# 3y-ym-2xxxy-psu-breakout.net
KiCad netlist of a schematic drawn in EAGLE
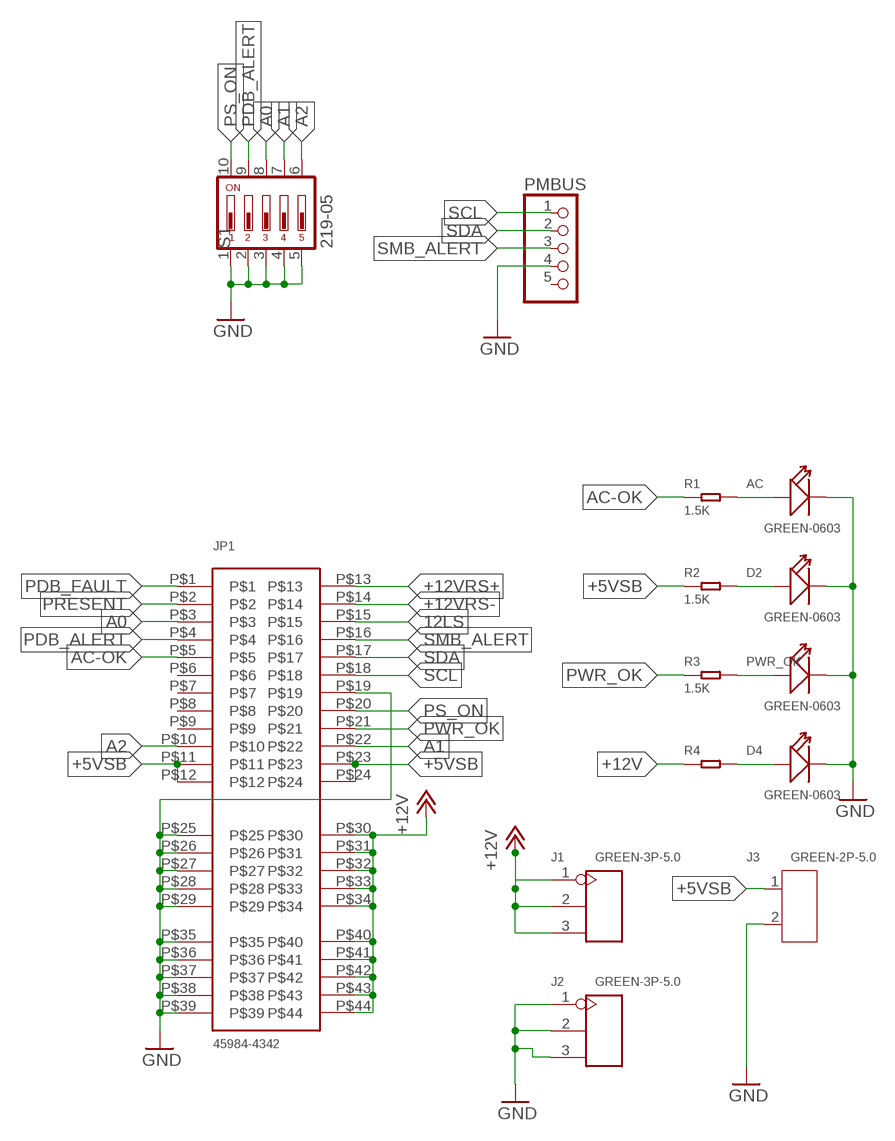
[diagram p0: schematic, sheet 1]

(export (version "E")
  (design (tool "Eeschema 10.0.6"))
  (components
    (comp (ref "AC")
      (value "GREEN-0603")
      (footprint "eagle-import:LED-0603")
      (fields (field (name "MPN") "19-217-G7C-AN1P2-3T"))
      (libsource (lib "eagle-import") (part "SMD-LED-CLEAR-GREEN(0603)"))
    )
    (comp (ref "D2")
      (value "GREEN-0603")
      (footprint "eagle-import:LED-0603")
      (fields (field (name "MPN") "19-217-G7C-AN1P2-3T"))
      (libsource (lib "eagle-import") (part "SMD-LED-CLEAR-GREEN(0603)"))
    )
    (comp (ref "D4")
      (value "GREEN-0603")
      (footprint "eagle-import:LED-0603")
      (fields (field (name "MPN") "19-217-G7C-AN1P2-3T"))
      (libsource (lib "eagle-import") (part "SMD-LED-CLEAR-GREEN(0603)"))
    )
    (comp (ref "J1")
      (value "GREEN-3P-5.0")
      (footprint "eagle-import:H3-5.0-15.5X8.0MM")
      (libsource (lib "eagle-import") (part "SCREW-TERMINAL-GREEN(3P-5.0)"))
    )
    (comp (ref "J2")
      (value "GREEN-3P-5.0")
      (footprint "eagle-import:H3-5.0-15.5X8.0MM")
      (libsource (lib "eagle-import") (part "SCREW-TERMINAL-GREEN(3P-5.0)"))
    )
    (comp (ref "J3")
      (value "GREEN-2P-5.0")
      (footprint "eagle-import:H2-5.0-10.5X8.0MM")
      (libsource (lib "eagle-import") (part "SCREW-TERMINAL-GREEN(2P-5.0)"))
    )
    (comp (ref "JP1")
      (value "45984-4342")
      (footprint "eagle-import:45984-4342")
      (libsource (lib "eagle-import") (part "45984-4342"))
    )
    (comp (ref "PMBUS")
      (value "PINHD-1X5")
      (footprint "eagle-import:1X05")
      (libsource (lib "eagle-import") (part "PINHD-1X5"))
    )
    (comp (ref "PWR_OK")
      (value "GREEN-0603")
      (footprint "eagle-import:LED-0603")
      (fields (field (name "MPN") "19-217-G7C-AN1P2-3T"))
      (libsource (lib "eagle-import") (part "SMD-LED-CLEAR-GREEN(0603)"))
    )
    (comp (ref "R1")
      (value "1.5K")
      (footprint "eagle-import:R0603")
      (fields (field (name "MPN") "RC0603FR-071K5L"))
      (libsource (lib "eagle-import") (part "SMD-RES-150R-1%-1/10W(0603)"))
    )
    (comp (ref "R2")
      (value "1.5K")
      (footprint "eagle-import:R0603")
      (fields (field (name "MPN") "RC0603FR-071K5L"))
      (libsource (lib "eagle-import") (part "SMD-RES-150R-1%-1/10W(0603)"))
    )
    (comp (ref "R3")
      (value "1.5K")
      (footprint "eagle-import:R0603")
      (fields (field (name "MPN") "RC0603FR-071K5L"))
      (libsource (lib "eagle-import") (part "SMD-RES-150R-1%-1/10W(0603)"))
    )
    (comp (ref "R4")
      (value "1.5K")
      (footprint "eagle-import:R0603")
      (libsource (lib "eagle-import") (part "SMD-RES-510R-1%-1/10W(0603)"))
    )
    (comp (ref "S1")
      (value "219-05")
      (footprint "eagle-import:CTS-219-05")
      (libsource (lib "eagle-import") (part "219-05"))
    )
  )
  (nets
    (net (code "1") (name "+5VSB") (class "Default")
      (node (ref "J3") (pin "1") (pinfunction "1_1") (pintype "bidirectional"))
      (node (ref "JP1") (pin "P$11") (pinfunction "P$11_P$11") (pintype "bidirectional"))
      (node (ref "JP1") (pin "P$12") (pinfunction "P$12_P$12") (pintype "bidirectional"))
      (node (ref "JP1") (pin "P$23") (pinfunction "P$23_P$23") (pintype "bidirectional"))
      (node (ref "JP1") (pin "P$24") (pinfunction "P$24_P$24") (pintype "bidirectional"))
      (node (ref "R2") (pin "1") (pinfunction "1_1") (pintype "passive"))
    )
    (net (code "2") (name "+12V") (class "Default")
      (node (ref "J1") (pin "1") (pinfunction "P$1_1") (pintype "bidirectional"))
      (node (ref "J1") (pin "2") (pinfunction "P$2_2") (pintype "bidirectional"))
      (node (ref "J1") (pin "3") (pinfunction "P$3_3") (pintype "bidirectional"))
      (node (ref "JP1") (pin "P$30") (pinfunction "P$30_P$30") (pintype "power_in"))
      (node (ref "JP1") (pin "P$31") (pinfunction "P$31_P$31") (pintype "power_in"))
      (node (ref "JP1") (pin "P$32") (pinfunction "P$32_P$32") (pintype "power_in"))
      (node (ref "JP1") (pin "P$33") (pinfunction "P$33_P$33") (pintype "power_in"))
      (node (ref "JP1") (pin "P$34") (pinfunction "P$34_P$34") (pintype "power_in"))
      (node (ref "JP1") (pin "P$40") (pinfunction "P$40_P$40") (pintype "power_in"))
      (node (ref "JP1") (pin "P$41") (pinfunction "P$41_P$41") (pintype "power_in"))
      (node (ref "JP1") (pin "P$42") (pinfunction "P$42_P$42") (pintype "power_in"))
      (node (ref "JP1") (pin "P$43") (pinfunction "P$43_P$43") (pintype "power_in"))
      (node (ref "JP1") (pin "P$44") (pinfunction "P$44_P$44") (pintype "power_in"))
      (node (ref "R4") (pin "1") (pinfunction "1_1") (pintype "passive"))
    )
    (net (code "3") (name "+12VRS+") (class "Default")
      (node (ref "JP1") (pin "P$13") (pinfunction "P$13_P$13") (pintype "bidirectional"))
    )
    (net (code "4") (name "+12VRS-") (class "Default")
      (node (ref "JP1") (pin "P$14") (pinfunction "P$14_P$14") (pintype "bidirectional"))
    )
    (net (code "5") (name "12LS") (class "Default")
      (node (ref "JP1") (pin "P$15") (pinfunction "P$15_P$15") (pintype "bidirectional"))
    )
    (net (code "6") (name "A0") (class "Default")
      (node (ref "JP1") (pin "P$3") (pinfunction "P$3_P$3") (pintype "bidirectional"))
      (node (ref "S1") (pin "8") (pinfunction "8_8") (pintype "passive"))
    )
    (net (code "7") (name "A1") (class "Default")
      (node (ref "JP1") (pin "P$22") (pinfunction "P$22_P$22") (pintype "bidirectional"))
      (node (ref "S1") (pin "7") (pinfunction "7_7") (pintype "passive"))
    )
    (net (code "8") (name "A2") (class "Default")
      (node (ref "JP1") (pin "P$10") (pinfunction "P$10_P$10") (pintype "bidirectional"))
      (node (ref "S1") (pin "6") (pinfunction "6_6") (pintype "passive"))
    )
    (net (code "9") (name "AC-OK") (class "Default")
      (node (ref "JP1") (pin "P$5") (pinfunction "P$5_P$5") (pintype "bidirectional"))
      (node (ref "R1") (pin "1") (pinfunction "1_1") (pintype "passive"))
    )
    (net (code "10") (name "GND") (class "Default")
      (node (ref "AC") (pin "-") (pinfunction "-_-") (pintype "passive"))
      (node (ref "D2") (pin "-") (pinfunction "-_-") (pintype "passive"))
      (node (ref "D4") (pin "-") (pinfunction "-_-") (pintype "passive"))
      (node (ref "J2") (pin "1") (pinfunction "P$1_1") (pintype "bidirectional"))
      (node (ref "J2") (pin "2") (pinfunction "P$2_2") (pintype "bidirectional"))
      (node (ref "J2") (pin "3") (pinfunction "P$3_3") (pintype "bidirectional"))
      (node (ref "J3") (pin "2") (pinfunction "2_2") (pintype "bidirectional"))
      (node (ref "JP1") (pin "P$19") (pinfunction "P$19_P$19") (pintype "bidirectional"))
      (node (ref "JP1") (pin "P$25") (pinfunction "P$25_P$25") (pintype "power_in"))
      (node (ref "JP1") (pin "P$26") (pinfunction "P$26_P$26") (pintype "power_in"))
      (node (ref "JP1") (pin "P$27") (pinfunction "P$27_P$27") (pintype "power_in"))
      (node (ref "JP1") (pin "P$28") (pinfunction "P$28_P$28") (pintype "power_in"))
      (node (ref "JP1") (pin "P$29") (pinfunction "P$29_P$29") (pintype "power_in"))
      (node (ref "JP1") (pin "P$35") (pinfunction "P$35_P$35") (pintype "power_in"))
      (node (ref "JP1") (pin "P$36") (pinfunction "P$36_P$36") (pintype "power_in"))
      (node (ref "JP1") (pin "P$37") (pinfunction "P$37_P$37") (pintype "power_in"))
      (node (ref "JP1") (pin "P$38") (pinfunction "P$38_P$38") (pintype "power_in"))
      (node (ref "JP1") (pin "P$39") (pinfunction "P$39_P$39") (pintype "power_in"))
      (node (ref "PMBUS") (pin "4") (pinfunction "4_4") (pintype "passive"))
      (node (ref "PWR_OK") (pin "-") (pinfunction "-_-") (pintype "passive"))
      (node (ref "S1") (pin "1") (pinfunction "1_1") (pintype "passive"))
      (node (ref "S1") (pin "2") (pinfunction "2_2") (pintype "passive"))
      (node (ref "S1") (pin "3") (pinfunction "3_3") (pintype "passive"))
      (node (ref "S1") (pin "4") (pinfunction "4_4") (pintype "passive"))
      (node (ref "S1") (pin "5") (pinfunction "5_5") (pintype "passive"))
    )
    (net (code "11") (name "Net-(AC-Pad+)") (class "Default")
      (node (ref "AC") (pin "+") (pinfunction "+_+") (pintype "passive"))
      (node (ref "R1") (pin "2") (pinfunction "2_2") (pintype "passive"))
    )
    (net (code "12") (name "Net-(D2-Pad+)") (class "Default")
      (node (ref "D2") (pin "+") (pinfunction "+_+") (pintype "passive"))
      (node (ref "R2") (pin "2") (pinfunction "2_2") (pintype "passive"))
    )
    (net (code "13") (name "Net-(D4-Pad+)") (class "Default")
      (node (ref "D4") (pin "+") (pinfunction "+_+") (pintype "passive"))
      (node (ref "R4") (pin "2") (pinfunction "2_2") (pintype "passive"))
    )
    (net (code "14") (name "Net-(PWR_OK-Pad+)") (class "Default")
      (node (ref "PWR_OK") (pin "+") (pinfunction "+_+") (pintype "passive"))
      (node (ref "R3") (pin "2") (pinfunction "2_2") (pintype "passive"))
    )
    (net (code "15") (name "PDB_ALERT") (class "Default")
      (node (ref "JP1") (pin "P$4") (pinfunction "P$4_P$4") (pintype "bidirectional"))
      (node (ref "S1") (pin "9") (pinfunction "9_9") (pintype "passive"))
    )
    (net (code "16") (name "PDB_FAULT") (class "Default")
      (node (ref "JP1") (pin "P$1") (pinfunction "P$1_P$1") (pintype "bidirectional"))
    )
    (net (code "17") (name "PRESENT") (class "Default")
      (node (ref "JP1") (pin "P$2") (pinfunction "P$2_P$2") (pintype "bidirectional"))
    )
    (net (code "18") (name "PS_ON") (class "Default")
      (node (ref "JP1") (pin "P$20") (pinfunction "P$20_P$20") (pintype "bidirectional"))
      (node (ref "S1") (pin "10") (pinfunction "10_10") (pintype "passive"))
    )
    (net (code "19") (name "PWR_OK") (class "Default")
      (node (ref "JP1") (pin "P$21") (pinfunction "P$21_P$21") (pintype "bidirectional"))
      (node (ref "R3") (pin "1") (pinfunction "1_1") (pintype "passive"))
    )
    (net (code "20") (name "SCL") (class "Default")
      (node (ref "JP1") (pin "P$18") (pinfunction "P$18_P$18") (pintype "bidirectional"))
      (node (ref "PMBUS") (pin "1") (pinfunction "1_1") (pintype "passive"))
    )
    (net (code "21") (name "SDA") (class "Default")
      (node (ref "JP1") (pin "P$17") (pinfunction "P$17_P$17") (pintype "bidirectional"))
      (node (ref "PMBUS") (pin "2") (pinfunction "2_2") (pintype "passive"))
    )
    (net (code "22") (name "SMB_ALERT") (class "Default")
      (node (ref "JP1") (pin "P$16") (pinfunction "P$16_P$16") (pintype "bidirectional"))
      (node (ref "PMBUS") (pin "3") (pinfunction "3_3") (pintype "passive"))
    )
    (net (code "23") (name "unconnected-(JP1-PadP$6)") (class "Default")
      (node (ref "JP1") (pin "P$6") (pinfunction "P$6_P$6") (pintype "bidirectional"))
    )
    (net (code "24") (name "unconnected-(JP1-PadP$7)") (class "Default")
      (node (ref "JP1") (pin "P$7") (pinfunction "P$7_P$7") (pintype "bidirectional"))
    )
    (net (code "25") (name "unconnected-(JP1-PadP$8)") (class "Default")
      (node (ref "JP1") (pin "P$8") (pinfunction "P$8_P$8") (pintype "bidirectional"))
    )
    (net (code "26") (name "unconnected-(JP1-PadP$9)") (class "Default")
      (node (ref "JP1") (pin "P$9") (pinfunction "P$9_P$9") (pintype "bidirectional"))
    )
    (net (code "27") (name "unconnected-(PMBUS-Pad5)") (class "Default")
      (node (ref "PMBUS") (pin "5") (pinfunction "5_5") (pintype "passive"))
    )
  )
)
